# EEPROM_ONLY_memory_board.net
KiCad netlist of a schematic drawn in EAGLE
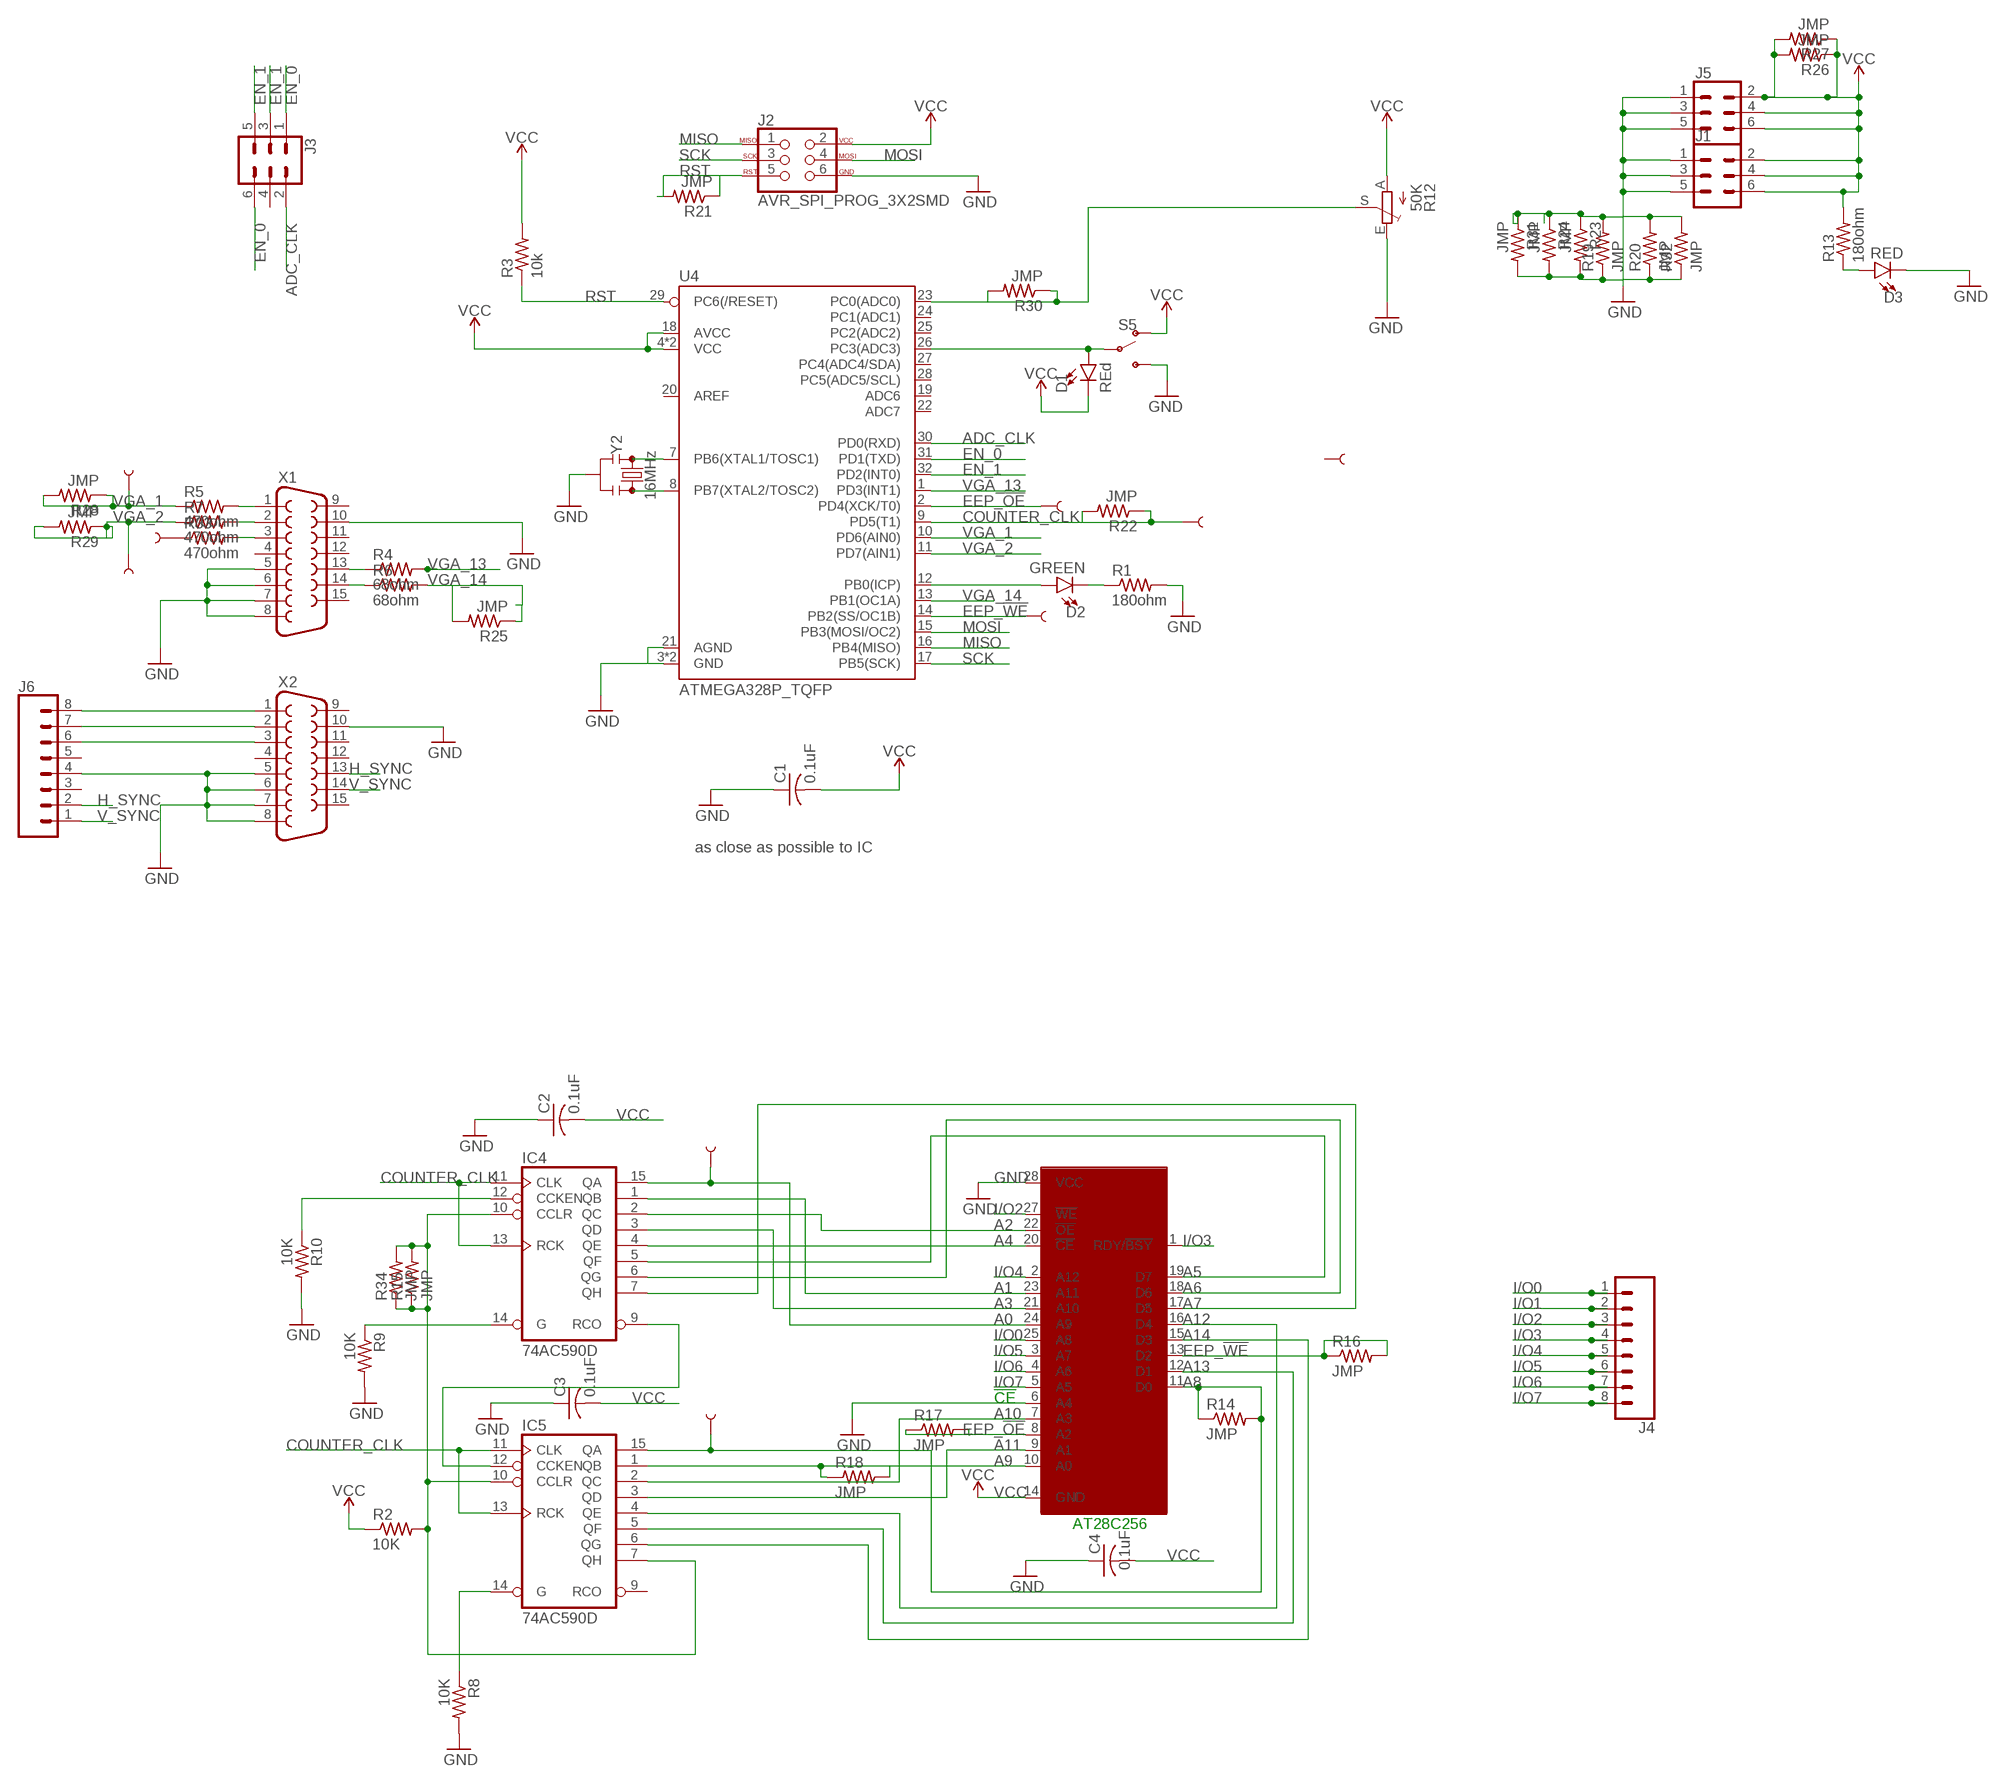
[diagram p0: schematic, sheet 1]

(export (version "E")
  (design (tool "Eeschema 10.0.6"))
  (components
    (comp (ref "C1")
      (value "0.1uF")
      (footprint "eagle-import:C1206")
      (libsource (lib "eagle-import") (part "C-USC1206"))
    )
    (comp (ref "C2")
      (value "0.1uF")
      (footprint "eagle-import:C1206")
      (libsource (lib "eagle-import") (part "C-USC1206"))
    )
    (comp (ref "C3")
      (value "0.1uF")
      (footprint "eagle-import:C1206")
      (libsource (lib "eagle-import") (part "C-USC1206"))
    )
    (comp (ref "C4")
      (value "0.1uF")
      (footprint "eagle-import:C1206")
      (libsource (lib "eagle-import") (part "C-USC1206"))
    )
    (comp (ref "D1")
      (value "REd")
      (footprint "eagle-import:LED-1206")
      (libsource (lib "eagle-import") (part "LED-RED1206"))
    )
    (comp (ref "D2")
      (value "GREEN")
      (footprint "eagle-import:LED-1206")
      (libsource (lib "eagle-import") (part "LED-RED1206"))
    )
    (comp (ref "D3")
      (value "RED")
      (footprint "eagle-import:LED-1206")
      (libsource (lib "eagle-import") (part "LED-RED1206"))
    )
    (comp (ref "IC1")
      (value "28C64AVS")
      (footprint "eagle-import:VSOP28-8X13")
      (libsource (lib "eagle-import") (part "2864AVSC"))
    )
    (comp (ref "IC4")
      (value "74AC590D")
      (footprint "eagle-import:SO16")
      (libsource (lib "eagle-import") (part "74590DAC"))
    )
    (comp (ref "IC5")
      (value "74AC590D")
      (footprint "eagle-import:SO16")
      (libsource (lib "eagle-import") (part "74590DAC"))
    )
    (comp (ref "J1")
      (value "CONN_03X2FEMALE_SMD")
      (footprint "eagle-import:2X3_SMD")
      (libsource (lib "eagle-import") (part "CONN_03X2FEMALE_SMD"))
    )
    (comp (ref "J2")
      (value "AVR_SPI_PROG_3X2SMD")
      (footprint "eagle-import:2X3_SMT_POSTS")
      (libsource (lib "eagle-import") (part "AVR_SPI_PROG_3X2SMD"))
    )
    (comp (ref "J3")
      (value "CONN_03X2FEMALE_SMD")
      (footprint "eagle-import:2X3_SMD")
      (libsource (lib "eagle-import") (part "CONN_03X2FEMALE_SMD"))
    )
    (comp (ref "J4")
      (value "CONN_08SMD-STRAIGHT-ALT-FEMALE")
      (footprint "eagle-import:1X08_SMD_ALT")
      (libsource (lib "eagle-import") (part "CONN_08SMD-STRAIGHT-ALT-FEMALE"))
    )
    (comp (ref "J5")
      (value "CONN_03X2FEMALE_SMD")
      (footprint "eagle-import:2X3_SMD")
      (libsource (lib "eagle-import") (part "CONN_03X2FEMALE_SMD"))
    )
    (comp (ref "J6")
      (value "CONN_08SMD-STRAIGHT-ALT-FEMALE")
      (footprint "eagle-import:1X08_SMD_ALT")
      (libsource (lib "eagle-import") (part "CONN_08SMD-STRAIGHT-ALT-FEMALE"))
    )
    (comp (ref "R1")
      (value "180ohm")
      (footprint "eagle-import:R1206")
      (libsource (lib "eagle-import") (part "R-US_R1206"))
    )
    (comp (ref "R2")
      (value "10K")
      (footprint "eagle-import:R1206")
      (libsource (lib "eagle-import") (part "R-US_R1206"))
    )
    (comp (ref "R3")
      (value "10k")
      (footprint "eagle-import:R1206")
      (libsource (lib "eagle-import") (part "R-US_R1206"))
    )
    (comp (ref "R4")
      (value "68ohm")
      (footprint "eagle-import:R1206")
      (libsource (lib "eagle-import") (part "R-US_R1206"))
    )
    (comp (ref "R5")
      (value "470ohm")
      (footprint "eagle-import:R1206")
      (libsource (lib "eagle-import") (part "R-US_R1206"))
    )
    (comp (ref "R6")
      (value "68ohm")
      (footprint "eagle-import:R1206")
      (libsource (lib "eagle-import") (part "R-US_R1206"))
    )
    (comp (ref "R7")
      (value "470ohm")
      (footprint "eagle-import:R1206")
      (libsource (lib "eagle-import") (part "R-US_R1206"))
    )
    (comp (ref "R8")
      (value "10K")
      (footprint "eagle-import:R1206")
      (libsource (lib "eagle-import") (part "R-US_R1206"))
    )
    (comp (ref "R9")
      (value "10K")
      (footprint "eagle-import:R1206")
      (libsource (lib "eagle-import") (part "R-US_R1206"))
    )
    (comp (ref "R10")
      (value "10K")
      (footprint "eagle-import:R1206")
      (libsource (lib "eagle-import") (part "R-US_R1206"))
    )
    (comp (ref "R12")
      (value "50K")
      (footprint "eagle-import:CA9V")
      (libsource (lib "eagle-import") (part "TRIM_EU-CA9V"))
    )
    (comp (ref "R13")
      (value "180ohm")
      (footprint "eagle-import:R1206")
      (libsource (lib "eagle-import") (part "R-US_R1206"))
    )
    (comp (ref "R14")
      (value "JMP")
      (footprint "eagle-import:R1206")
      (libsource (lib "eagle-import") (part "R-US_R1206"))
    )
    (comp (ref "R15")
      (value "JMP")
      (footprint "eagle-import:R1206")
      (libsource (lib "eagle-import") (part "R-US_R1206"))
    )
    (comp (ref "R16")
      (value "JMP")
      (footprint "eagle-import:R1206")
      (libsource (lib "eagle-import") (part "R-US_R1206"))
    )
    (comp (ref "R17")
      (value "JMP")
      (footprint "eagle-import:R1206")
      (libsource (lib "eagle-import") (part "R-US_R1206"))
    )
    (comp (ref "R18")
      (value "JMP")
      (footprint "eagle-import:R1206")
      (libsource (lib "eagle-import") (part "R-US_R1206"))
    )
    (comp (ref "R19")
      (value "JMP")
      (footprint "eagle-import:R1206")
      (libsource (lib "eagle-import") (part "R-US_R1206"))
    )
    (comp (ref "R20")
      (value "JMP")
      (footprint "eagle-import:R1206")
      (libsource (lib "eagle-import") (part "R-US_R1206"))
    )
    (comp (ref "R21")
      (value "JMP")
      (footprint "eagle-import:R1206")
      (libsource (lib "eagle-import") (part "R-US_R1206"))
    )
    (comp (ref "R22")
      (value "JMP")
      (footprint "eagle-import:R1206")
      (libsource (lib "eagle-import") (part "R-US_R1206"))
    )
    (comp (ref "R23")
      (value "JMP")
      (footprint "eagle-import:R1206")
      (libsource (lib "eagle-import") (part "R-US_R1206"))
    )
    (comp (ref "R24")
      (value "JMP")
      (footprint "eagle-import:R1206")
      (libsource (lib "eagle-import") (part "R-US_R1206"))
    )
    (comp (ref "R25")
      (value "JMP")
      (footprint "eagle-import:R1206")
      (libsource (lib "eagle-import") (part "R-US_R1206"))
    )
    (comp (ref "R26")
      (value "JMP")
      (footprint "eagle-import:R1206")
      (libsource (lib "eagle-import") (part "R-US_R1206"))
    )
    (comp (ref "R27")
      (value "JMP")
      (footprint "eagle-import:R1206")
      (libsource (lib "eagle-import") (part "R-US_R1206"))
    )
    (comp (ref "R28")
      (value "JMP")
      (footprint "eagle-import:R1206")
      (libsource (lib "eagle-import") (part "R-US_R1206"))
    )
    (comp (ref "R29")
      (value "JMP")
      (footprint "eagle-import:R1206")
      (libsource (lib "eagle-import") (part "R-US_R1206"))
    )
    (comp (ref "R30")
      (value "JMP")
      (footprint "eagle-import:R1206")
      (libsource (lib "eagle-import") (part "R-US_R1206"))
    )
    (comp (ref "R31")
      (value "JMP")
      (footprint "eagle-import:R1206")
      (libsource (lib "eagle-import") (part "R-US_R1206"))
    )
    (comp (ref "R32")
      (value "JMP")
      (footprint "eagle-import:R1206")
      (libsource (lib "eagle-import") (part "R-US_R1206"))
    )
    (comp (ref "R33")
      (value "470ohm")
      (footprint "eagle-import:R1206")
      (libsource (lib "eagle-import") (part "R-US_R1206"))
    )
    (comp (ref "R34")
      (value "JMP")
      (footprint "eagle-import:R1206")
      (libsource (lib "eagle-import") (part "R-US_R1206"))
    )
    (comp (ref "RX1")
      (value "TEST-POINT3")
      (footprint "eagle-import:PAD.03X.03")
      (libsource (lib "eagle-import") (part "TEST-POINT3"))
    )
    (comp (ref "RX2")
      (value "TEST-POINT3")
      (footprint "eagle-import:PAD.03X.03")
      (libsource (lib "eagle-import") (part "TEST-POINT3"))
    )
    (comp (ref "RX3")
      (value "TEST-POINT3")
      (footprint "eagle-import:PAD.03X.03")
      (libsource (lib "eagle-import") (part "TEST-POINT3"))
    )
    (comp (ref "RX4")
      (value "TEST-POINT3")
      (footprint "eagle-import:PAD.03X.03")
      (libsource (lib "eagle-import") (part "TEST-POINT3"))
    )
    (comp (ref "RX5")
      (value "TEST-POINT3")
      (footprint "eagle-import:PAD.03X.03")
      (libsource (lib "eagle-import") (part "TEST-POINT3"))
    )
    (comp (ref "RX6")
      (value "TEST-POINT3")
      (footprint "eagle-import:PAD.03X.03")
      (libsource (lib "eagle-import") (part "TEST-POINT3"))
    )
    (comp (ref "RX7")
      (value "TEST-POINT3")
      (footprint "eagle-import:PAD.03X.03")
      (libsource (lib "eagle-import") (part "TEST-POINT3"))
    )
    (comp (ref "RX8")
      (value "TEST-POINT3")
      (footprint "eagle-import:PAD.03X.03")
      (libsource (lib "eagle-import") (part "TEST-POINT3"))
    )
    (comp (ref "RX9")
      (value "TEST-POINT3")
      (footprint "eagle-import:PAD.03X.03")
      (libsource (lib "eagle-import") (part "TEST-POINT3"))
    )
    (comp (ref "S5")
      (value "SWITCH-SPDT-SMD-AYZ0202")
      (footprint "eagle-import:SWITCH_DPDT_SMD_AYZ0202")
      (libsource (lib "eagle-import") (part "SWITCH-SPDT-SMD-AYZ0202"))
    )
    (comp (ref "U4")
      (value "ATMEGA328P_TQFP")
      (footprint "eagle-import:TQFP32-08")
      (libsource (lib "eagle-import") (part "ATMEGA328P_TQFP"))
    )
    (comp (ref "X1")
      (value "F15HP")
      (footprint "eagle-import:F15HP")
      (libsource (lib "eagle-import") (part "F15HP"))
    )
    (comp (ref "X2")
      (value "F15HP")
      (footprint "eagle-import:F15HP")
      (libsource (lib "eagle-import") (part "F15HP"))
    )
    (comp (ref "Y2")
      (value "16MHz")
      (footprint "eagle-import:RESONATOR-SMD-3.2X1.3")
      (libsource (lib "eagle-import") (part "RESONATOR-16MHZSMD_3.2X1.3"))
    )
  )
  (nets
    (net (code "1") (name "/A0") (class "Default")
      (node (ref "IC1") (pin "24") (pinfunction "A9_24") (pintype "input"))
      (node (ref "IC4") (pin "15") (pinfunction "QA_15") (pintype "tri_state"))
      (node (ref "RX5") (pin "P$1") (pinfunction "1_P$1") (pintype "bidirectional"))
    )
    (net (code "2") (name "/A1") (class "Default")
      (node (ref "IC1") (pin "23") (pinfunction "A11_23") (pintype "input"))
      (node (ref "IC4") (pin "1") (pinfunction "QB_1") (pintype "tri_state"))
    )
    (net (code "3") (name "/A2") (class "Default")
      (node (ref "IC1") (pin "22") (pinfunction "~{OE}_22") (pintype "input"))
      (node (ref "IC4") (pin "2") (pinfunction "QC_2") (pintype "tri_state"))
    )
    (net (code "4") (name "/A3") (class "Default")
      (node (ref "IC1") (pin "21") (pinfunction "A10_21") (pintype "input"))
      (node (ref "IC4") (pin "3") (pinfunction "QD_3") (pintype "tri_state"))
    )
    (net (code "5") (name "/A4") (class "Default")
      (node (ref "IC1") (pin "20") (pinfunction "~{CE}_20") (pintype "input"))
      (node (ref "IC4") (pin "4") (pinfunction "QE_4") (pintype "tri_state"))
    )
    (net (code "6") (name "/A5") (class "Default")
      (node (ref "IC1") (pin "19") (pinfunction "D7_19") (pintype "tri_state"))
      (node (ref "IC4") (pin "5") (pinfunction "QF_5") (pintype "tri_state"))
    )
    (net (code "7") (name "/A6") (class "Default")
      (node (ref "IC1") (pin "18") (pinfunction "D6_18") (pintype "tri_state"))
      (node (ref "IC4") (pin "6") (pinfunction "QG_6") (pintype "tri_state"))
    )
    (net (code "8") (name "/A7") (class "Default")
      (node (ref "IC1") (pin "17") (pinfunction "D5_17") (pintype "tri_state"))
      (node (ref "IC4") (pin "7") (pinfunction "QH_7") (pintype "tri_state"))
    )
    (net (code "9") (name "/A8") (class "Default")
      (node (ref "IC1") (pin "11") (pinfunction "D0_11") (pintype "tri_state"))
      (node (ref "IC5") (pin "15") (pinfunction "QA_15") (pintype "tri_state"))
      (node (ref "R14") (pin "1") (pinfunction "1_1") (pintype "passive"))
      (node (ref "R14") (pin "2") (pinfunction "2_2") (pintype "passive"))
      (node (ref "RX6") (pin "P$1") (pinfunction "1_P$1") (pintype "bidirectional"))
    )
    (net (code "10") (name "/A9") (class "Default")
      (node (ref "IC1") (pin "10") (pinfunction "A0_10") (pintype "input"))
      (node (ref "IC5") (pin "1") (pinfunction "QB_1") (pintype "tri_state"))
      (node (ref "R18") (pin "1") (pinfunction "1_1") (pintype "passive"))
      (node (ref "R18") (pin "2") (pinfunction "2_2") (pintype "passive"))
    )
    (net (code "11") (name "/A10") (class "Default")
      (node (ref "IC1") (pin "7") (pinfunction "A3_7") (pintype "input"))
      (node (ref "IC5") (pin "2") (pinfunction "QC_2") (pintype "tri_state"))
    )
    (net (code "12") (name "/A11") (class "Default")
      (node (ref "IC1") (pin "9") (pinfunction "A1_9") (pintype "input"))
      (node (ref "IC5") (pin "3") (pinfunction "QD_3") (pintype "tri_state"))
    )
    (net (code "13") (name "/A12") (class "Default")
      (node (ref "IC1") (pin "16") (pinfunction "D4_16") (pintype "tri_state"))
      (node (ref "IC5") (pin "4") (pinfunction "QE_4") (pintype "tri_state"))
    )
    (net (code "14") (name "/A13") (class "Default")
      (node (ref "IC1") (pin "12") (pinfunction "D1_12") (pintype "tri_state"))
      (node (ref "IC5") (pin "5") (pinfunction "QF_5") (pintype "tri_state"))
    )
    (net (code "15") (name "/A14") (class "Default")
      (node (ref "IC1") (pin "15") (pinfunction "D3_15") (pintype "tri_state"))
      (node (ref "IC5") (pin "6") (pinfunction "QG_6") (pintype "tri_state"))
    )
    (net (code "16") (name "/ADC_CLK") (class "Default")
      (node (ref "J3") (pin "2") (pinfunction "2_2") (pintype "bidirectional"))
      (node (ref "U4") (pin "30") (pinfunction "PD0(RXD)_30") (pintype "bidirectional"))
    )
    (net (code "17") (name "/COUNTER_CLK") (class "Default")
      (node (ref "IC4") (pin "11") (pinfunction "CLK_11") (pintype "input"))
      (node (ref "IC4") (pin "13") (pinfunction "RCK_13") (pintype "input"))
      (node (ref "IC5") (pin "11") (pinfunction "CLK_11") (pintype "input"))
      (node (ref "IC5") (pin "13") (pinfunction "RCK_13") (pintype "input"))
      (node (ref "R22") (pin "1") (pinfunction "1_1") (pintype "passive"))
      (node (ref "R22") (pin "2") (pinfunction "2_2") (pintype "passive"))
      (node (ref "RX3") (pin "P$1") (pinfunction "1_P$1") (pintype "bidirectional"))
      (node (ref "U4") (pin "9") (pinfunction "PD5(T1)_9") (pintype "bidirectional"))
    )
    (net (code "18") (name "/EEP_~{OE}") (class "Default")
      (node (ref "IC1") (pin "8") (pinfunction "A2_8") (pintype "input"))
      (node (ref "R17") (pin "1") (pinfunction "1_1") (pintype "passive"))
      (node (ref "R17") (pin "2") (pinfunction "2_2") (pintype "passive"))
      (node (ref "RX2") (pin "P$1") (pinfunction "1_P$1") (pintype "bidirectional"))
      (node (ref "U4") (pin "2") (pinfunction "PD4(XCK/T0)_2") (pintype "bidirectional"))
    )
    (net (code "19") (name "/EEP_~{WE}") (class "Default")
      (node (ref "IC1") (pin "13") (pinfunction "D2_13") (pintype "tri_state"))
      (node (ref "R16") (pin "1") (pinfunction "1_1") (pintype "passive"))
      (node (ref "R16") (pin "2") (pinfunction "2_2") (pintype "passive"))
      (node (ref "RX4") (pin "P$1") (pinfunction "1_P$1") (pintype "bidirectional"))
      (node (ref "U4") (pin "14") (pinfunction "PB2(SS/OC1B)_14") (pintype "bidirectional"))
    )
    (net (code "20") (name "/EN_0") (class "Default")
      (node (ref "J3") (pin "1") (pinfunction "1_1") (pintype "bidirectional"))
      (node (ref "J3") (pin "6") (pinfunction "6_6") (pintype "bidirectional"))
      (node (ref "U4") (pin "31") (pinfunction "PD1(TXD)_31") (pintype "bidirectional"))
    )
    (net (code "21") (name "/EN_1") (class "Default")
      (node (ref "J3") (pin "3") (pinfunction "3_3") (pintype "bidirectional"))
      (node (ref "J3") (pin "5") (pinfunction "5_5") (pintype "bidirectional"))
      (node (ref "U4") (pin "32") (pinfunction "PD2(INT0)_32") (pintype "bidirectional"))
    )
    (net (code "22") (name "/H_SYNC") (class "Default")
      (node (ref "J6") (pin "2") (pinfunction "2_2") (pintype "passive"))
      (node (ref "X2") (pin "13") (pinfunction "13_13") (pintype "passive"))
    )
    (net (code "23") (name "/I{slash}O0") (class "Default")
      (node (ref "IC1") (pin "25") (pinfunction "A8_25") (pintype "input"))
      (node (ref "J4") (pin "1") (pinfunction "1_1") (pintype "passive"))
    )
    (net (code "24") (name "/I{slash}O1") (class "Default")
      (node (ref "J4") (pin "2") (pinfunction "2_2") (pintype "passive"))
    )
    (net (code "25") (name "/I{slash}O2") (class "Default")
      (node (ref "IC1") (pin "27") (pinfunction "~{WE}_27") (pintype "input"))
      (node (ref "J4") (pin "3") (pinfunction "3_3") (pintype "passive"))
    )
    (net (code "26") (name "/I{slash}O3") (class "Default")
      (node (ref "IC1") (pin "1") (pinfunction "RDY/~{BSY}_1") (pintype "output"))
      (node (ref "J4") (pin "4") (pinfunction "4_4") (pintype "passive"))
    )
    (net (code "27") (name "/I{slash}O4") (class "Default")
      (node (ref "IC1") (pin "2") (pinfunction "A12_2") (pintype "input"))
      (node (ref "J4") (pin "5") (pinfunction "5_5") (pintype "passive"))
    )
    (net (code "28") (name "/I{slash}O5") (class "Default")
      (node (ref "IC1") (pin "3") (pinfunction "A7_3") (pintype "input"))
      (node (ref "J4") (pin "6") (pinfunction "6_6") (pintype "passive"))
    )
    (net (code "29") (name "/I{slash}O6") (class "Default")
      (node (ref "IC1") (pin "4") (pinfunction "A6_4") (pintype "input"))
      (node (ref "J4") (pin "7") (pinfunction "7_7") (pintype "passive"))
    )
    (net (code "30") (name "/I{slash}O7") (class "Default")
      (node (ref "IC1") (pin "5") (pinfunction "A5_5") (pintype "input"))
      (node (ref "J4") (pin "8") (pinfunction "8_8") (pintype "passive"))
    )
    (net (code "31") (name "/MISO") (class "Default")
      (node (ref "J2") (pin "1") (pinfunction "1_1") (pintype "passive"))
      (node (ref "U4") (pin "16") (pinfunction "PB4(MISO)_16") (pintype "bidirectional"))
    )
    (net (code "32") (name "/MOSI") (class "Default")
      (node (ref "J2") (pin "4") (pinfunction "4_4") (pintype "passive"))
      (node (ref "U4") (pin "15") (pinfunction "PB3(MOSI/OC2)_15") (pintype "bidirectional"))
    )
    (net (code "33") (name "/RST") (class "Default")
      (node (ref "J2") (pin "5") (pinfunction "5_5") (pintype "passive"))
      (node (ref "R21") (pin "1") (pinfunction "1_1") (pintype "passive"))
      (node (ref "R21") (pin "2") (pinfunction "2_2") (pintype "passive"))
      (node (ref "R3") (pin "1") (pinfunction "1_1") (pintype "passive"))
      (node (ref "U4") (pin "29") (pinfunction "PC6(/RESET)_29") (pintype "bidirectional"))
    )
    (net (code "34") (name "/SCK") (class "Default")
      (node (ref "J2") (pin "3") (pinfunction "3_3") (pintype "passive"))
      (node (ref "U4") (pin "17") (pinfunction "PB5(SCK)_17") (pintype "bidirectional"))
    )
    (net (code "35") (name "/VGA_1") (class "Default")
      (node (ref "R28") (pin "1") (pinfunction "1_1") (pintype "passive"))
      (node (ref "R28") (pin "2") (pinfunction "2_2") (pintype "passive"))
      (node (ref "R5") (pin "1") (pinfunction "1_1") (pintype "passive"))
      (node (ref "RX8") (pin "P$1") (pinfunction "1_P$1") (pintype "bidirectional"))
      (node (ref "U4") (pin "10") (pinfunction "PD6(AIN0)_10") (pintype "bidirectional"))
    )
    (net (code "36") (name "/VGA_2") (class "Default")
      (node (ref "R29") (pin "1") (pinfunction "1_1") (pintype "passive"))
      (node (ref "R29") (pin "2") (pinfunction "2_2") (pintype "passive"))
      (node (ref "R7") (pin "1") (pinfunction "1_1") (pintype "passive"))
      (node (ref "RX9") (pin "P$1") (pinfunction "1_P$1") (pintype "bidirectional"))
      (node (ref "U4") (pin "11") (pinfunction "PD7(AIN1)_11") (pintype "bidirectional"))
    )
    (net (code "37") (name "/VGA_13") (class "Default")
      (node (ref "R4") (pin "2") (pinfunction "2_2") (pintype "passive"))
      (node (ref "U4") (pin "1") (pinfunction "PD3(INT1)_1") (pintype "bidirectional"))
    )
    (net (code "38") (name "/VGA_14") (class "Default")
      (node (ref "R25") (pin "1") (pinfunction "1_1") (pintype "passive"))
      (node (ref "R25") (pin "2") (pinfunction "2_2") (pintype "passive"))
      (node (ref "R6") (pin "2") (pinfunction "2_2") (pintype "passive"))
      (node (ref "U4") (pin "13") (pinfunction "PB1(OC1A)_13") (pintype "bidirectional"))
    )
    (net (code "39") (name "/V_SYNC") (class "Default")
      (node (ref "J6") (pin "1") (pinfunction "1_1") (pintype "passive"))
      (node (ref "X2") (pin "14") (pinfunction "14_14") (pintype "passive"))
    )
    (net (code "40") (name "GND") (class "Default")
      (node (ref "C1") (pin "1") (pinfunction "1_1") (pintype "passive"))
      (node (ref "C2") (pin "1") (pinfunction "1_1") (pintype "passive"))
      (node (ref "C3") (pin "1") (pinfunction "1_1") (pintype "passive"))
      (node (ref "C4") (pin "1") (pinfunction "1_1") (pintype "passive"))
      (node (ref "D3") (pin "C") (pinfunction "C_C") (pintype "passive"))
      (node (ref "IC1") (pin "28") (pinfunction "VCC_28") (pintype "power_in"))
      (node (ref "IC1") (pin "6") (pinfunction "A4_6") (pintype "input"))
      (node (ref "J1") (pin "1") (pinfunction "1_1") (pintype "bidirectional"))
      (node (ref "J1") (pin "3") (pinfunction "3_3") (pintype "bidirectional"))
      (node (ref "J1") (pin "5") (pinfunction "5_5") (pintype "bidirectional"))
      (node (ref "J2") (pin "6") (pinfunction "6_6") (pintype "passive"))
      (node (ref "J5") (pin "1") (pinfunction "1_1") (pintype "bidirectional"))
      (node (ref "J5") (pin "3") (pinfunction "3_3") (pintype "bidirectional"))
      (node (ref "J5") (pin "5") (pinfunction "5_5") (pintype "bidirectional"))
      (node (ref "J6") (pin "4") (pinfunction "4_4") (pintype "passive"))
      (node (ref "R1") (pin "2") (pinfunction "2_2") (pintype "passive"))
      (node (ref "R10") (pin "2") (pinfunction "2_2") (pintype "passive"))
      (node (ref "R12") (pin "E") (pinfunction "E_E") (pintype "passive"))
      (node (ref "R19") (pin "1") (pinfunction "1_1") (pintype "passive"))
      (node (ref "R19") (pin "2") (pinfunction "2_2") (pintype "passive"))
      (node (ref "R20") (pin "1") (pinfunction "1_1") (pintype "passive"))
      (node (ref "R20") (pin "2") (pinfunction "2_2") (pintype "passive"))
      (node (ref "R23") (pin "1") (pinfunction "1_1") (pintype "passive"))
      (node (ref "R23") (pin "2") (pinfunction "2_2") (pintype "passive"))
      (node (ref "R24") (pin "1") (pinfunction "1_1") (pintype "passive"))
      (node (ref "R24") (pin "2") (pinfunction "2_2") (pintype "passive"))
      (node (ref "R31") (pin "1") (pinfunction "1_1") (pintype "passive"))
      (node (ref "R31") (pin "2") (pinfunction "2_2") (pintype "passive"))
      (node (ref "R32") (pin "1") (pinfunction "1_1") (pintype "passive"))
      (node (ref "R32") (pin "2") (pinfunction "2_2") (pintype "passive"))
      (node (ref "R8") (pin "2") (pinfunction "2_2") (pintype "passive"))
      (node (ref "R9") (pin "2") (pinfunction "2_2") (pintype "passive"))
      (node (ref "S5") (pin "3") (pinfunction "S_3") (pintype "passive"))
      (node (ref "U4") (pin "21") (pinfunction "AGND_21") (pintype "bidirectional"))
      (node (ref "U4") (pin "3") (pinfunction "GND_3") (pintype "bidirectional"))
      (node (ref "U4") (pin "5") (pinfunction "GND_5") (pintype "bidirectional"))
      (node (ref "X1") (pin "10") (pinfunction "10_10") (pintype "passive"))
      (node (ref "X1") (pin "5") (pinfunction "5_5") (pintype "passive"))
      (node (ref "X1") (pin "6") (pinfunction "6_6") (pintype "passive"))
      (node (ref "X1") (pin "7") (pinfunction "7_7") (pintype "passive"))
      (node (ref "X1") (pin "8") (pinfunction "8_8") (pintype "passive"))
      (node (ref "X2") (pin "10") (pinfunction "10_10") (pintype "passive"))
      (node (ref "X2") (pin "5") (pinfunction "5_5") (pintype "passive"))
      (node (ref "X2") (pin "6") (pinfunction "6_6") (pintype "passive"))
      (node (ref "X2") (pin "7") (pinfunction "7_7") (pintype "passive"))
      (node (ref "X2") (pin "8") (pinfunction "8_8") (pintype "passive"))
      (node (ref "Y2") (pin "2") (pinfunction "2_2") (pintype "passive"))
    )
    (net (code "41") (name "Net-(D2-PadC)") (class "Default")
      (node (ref "D2") (pin "C") (pinfunction "C_C") (pintype "passive"))
      (node (ref "R1") (pin "1") (pinfunction "1_1") (pintype "passive"))
    )
    (net (code "42") (name "Net-(D3-PadA)") (class "Default")
      (node (ref "D3") (pin "A") (pinfunction "A_A") (pintype "passive"))
      (node (ref "R13") (pin "1") (pinfunction "1_1") (pintype "passive"))
    )
    (net (code "43") (name "Net-(IC4A-CCKEN)") (class "Default")
      (node (ref "IC4") (pin "12") (pinfunction "CCKEN_12") (pintype "input"))
      (node (ref "R10") (pin "1") (pinfunction "1_1") (pintype "passive"))
    )
    (net (code "44") (name "Net-(IC4A-CCLR)") (class "Default")
      (node (ref "IC4") (pin "10") (pinfunction "CCLR_10") (pintype "input"))
      (node (ref "IC5") (pin "10") (pinfunction "CCLR_10") (pintype "input"))
      (node (ref "IC5") (pin "7") (pinfunction "QH_7") (pintype "tri_state"))
      (node (ref "R15") (pin "1") (pinfunction "1_1") (pintype "passive"))
      (node (ref "R15") (pin "2") (pinfunction "2_2") (pintype "passive"))
      (node (ref "R2") (pin "2") (pinfunction "2_2") (pintype "passive"))
      (node (ref "R34") (pin "1") (pinfunction "1_1") (pintype "passive"))
      (node (ref "R34") (pin "2") (pinfunction "2_2") (pintype "passive"))
    )
    (net (code "45") (name "Net-(IC4A-G)") (class "Default")
      (node (ref "IC4") (pin "14") (pinfunction "G_14") (pintype "input"))
      (node (ref "R9") (pin "1") (pinfunction "1_1") (pintype "passive"))
    )
    (net (code "46") (name "Net-(IC4A-RCO)") (class "Default")
      (node (ref "IC4") (pin "9") (pinfunction "RCO_9") (pintype "output"))
      (node (ref "IC5") (pin "12") (pinfunction "CCKEN_12") (pintype "input"))
    )
    (net (code "47") (name "Net-(IC5A-G)") (class "Default")
      (node (ref "IC5") (pin "14") (pinfunction "G_14") (pintype "input"))
      (node (ref "R8") (pin "1") (pinfunction "1_1") (pintype "passive"))
    )
    (net (code "48") (name "Net-(J6-Pad6)") (class "Default")
      (node (ref "J6") (pin "6") (pinfunction "6_6") (pintype "passive"))
      (node (ref "X2") (pin "3") (pinfunction "3_3") (pintype "passive"))
    )
    (net (code "49") (name "Net-(J6-Pad7)") (class "Default")
      (node (ref "J6") (pin "7") (pinfunction "7_7") (pintype "passive"))
      (node (ref "X2") (pin "2") (pinfunction "2_2") (pintype "passive"))
    )
    (net (code "50") (name "Net-(J6-Pad8)") (class "Default")
      (node (ref "J6") (pin "8") (pinfunction "8_8") (pintype "passive"))
      (node (ref "X2") (pin "1") (pinfunction "1_1") (pintype "passive"))
    )
    (net (code "51") (name "Net-(R4-Pad1)") (class "Default")
      (node (ref "R4") (pin "1") (pinfunction "1_1") (pintype "passive"))
      (node (ref "X1") (pin "13") (pinfunction "13_13") (pintype "passive"))
    )
    (net (code "52") (name "Net-(R5-Pad2)") (class "Default")
      (node (ref "R5") (pin "2") (pinfunction "2_2") (pintype "passive"))
      (node (ref "X1") (pin "1") (pinfunction "1_1") (pintype "passive"))
    )
    (net (code "53") (name "Net-(R6-Pad1)") (class "Default")
      (node (ref "R6") (pin "1") (pinfunction "1_1") (pintype "passive"))
      (node (ref "X1") (pin "14") (pinfunction "14_14") (pintype "passive"))
    )
    (net (code "54") (name "Net-(R7-Pad2)") (class "Default")
      (node (ref "R7") (pin "2") (pinfunction "2_2") (pintype "passive"))
      (node (ref "X1") (pin "2") (pinfunction "2_2") (pintype "passive"))
    )
    (net (code "55") (name "Net-(R33-Pad2)") (class "Default")
      (node (ref "R33") (pin "2") (pinfunction "2_2") (pintype "passive"))
      (node (ref "X1") (pin "3") (pinfunction "3_3") (pintype "passive"))
    )
    (net (code "56") (name "Net-(RX7-1)") (class "Default")
      (node (ref "R33") (pin "1") (pinfunction "1_1") (pintype "passive"))
      (node (ref "RX7") (pin "P$1") (pinfunction "1_P$1") (pintype "bidirectional"))
    )
    (net (code "57") (name "Net-(S5-P)") (class "Default")
      (node (ref "D1") (pin "A") (pinfunction "A_A") (pintype "passive"))
      (node (ref "S5") (pin "2") (pinfunction "P_2") (pintype "passive"))
      (node (ref "U4") (pin "26") (pinfunction "PC3(ADC3)_26") (pintype "bidirectional"))
    )
    (net (code "58") (name "Net-(U4-PB0(ICP))") (class "Default")
      (node (ref "D2") (pin "A") (pinfunction "A_A") (pintype "passive"))
      (node (ref "U4") (pin "12") (pinfunction "PB0(ICP)_12") (pintype "bidirectional"))
    )
    (net (code "59") (name "Net-(U4-PB6(XTAL1{slash}TOSC1))") (class "Default")
      (node (ref "U4") (pin "7") (pinfunction "PB6(XTAL1/TOSC1)_7") (pintype "bidirectional"))
      (node (ref "Y2") (pin "1") (pinfunction "1_1") (pintype "passive"))
    )
    (net (code "60") (name "Net-(U4-PB7(XTAL2{slash}TOSC2))") (class "Default")
      (node (ref "U4") (pin "8") (pinfunction "PB7(XTAL2/TOSC2)_8") (pintype "bidirectional"))
      (node (ref "Y2") (pin "3") (pinfunction "3_3") (pintype "passive"))
    )
    (net (code "61") (name "Net-(U4-PC0(ADC0))") (class "Default")
      (node (ref "R12") (pin "S") (pinfunction "S_S") (pintype "passive"))
      (node (ref "R30") (pin "1") (pinfunction "1_1") (pintype "passive"))
      (node (ref "R30") (pin "2") (pinfunction "2_2") (pintype "passive"))
      (node (ref "U4") (pin "23") (pinfunction "PC0(ADC0)_23") (pintype "bidirectional"))
    )
    (net (code "62") (name "VCC") (class "Default")
      (node (ref "C1") (pin "2") (pinfunction "2_2") (pintype "passive"))
      (node (ref "C2") (pin "2") (pinfunction "2_2") (pintype "passive"))
      (node (ref "C3") (pin "2") (pinfunction "2_2") (pintype "passive"))
      (node (ref "C4") (pin "2") (pinfunction "2_2") (pintype "passive"))
      (node (ref "D1") (pin "C") (pinfunction "C_C") (pintype "passive"))
      (node (ref "IC1") (pin "14") (pinfunction "GND_14") (pintype "power_in"))
      (node (ref "J1") (pin "2") (pinfunction "2_2") (pintype "bidirectional"))
      (node (ref "J1") (pin "4") (pinfunction "4_4") (pintype "bidirectional"))
      (node (ref "J1") (pin "6") (pinfunction "6_6") (pintype "bidirectional"))
      (node (ref "J2") (pin "2") (pinfunction "2_2") (pintype "passive"))
      (node (ref "J5") (pin "2") (pinfunction "2_2") (pintype "bidirectional"))
      (node (ref "J5") (pin "4") (pinfunction "4_4") (pintype "bidirectional"))
      (node (ref "J5") (pin "6") (pinfunction "6_6") (pintype "bidirectional"))
      (node (ref "R12") (pin "A") (pinfunction "A_A") (pintype "passive"))
      (node (ref "R13") (pin "2") (pinfunction "2_2") (pintype "passive"))
      (node (ref "R2") (pin "1") (pinfunction "1_1") (pintype "passive"))
      (node (ref "R26") (pin "1") (pinfunction "1_1") (pintype "passive"))
      (node (ref "R26") (pin "2") (pinfunction "2_2") (pintype "passive"))
      (node (ref "R27") (pin "1") (pinfunction "1_1") (pintype "passive"))
      (node (ref "R27") (pin "2") (pinfunction "2_2") (pintype "passive"))
      (node (ref "R3") (pin "2") (pinfunction "2_2") (pintype "passive"))
      (node (ref "S5") (pin "1") (pinfunction "O_1") (pintype "passive"))
      (node (ref "U4") (pin "18") (pinfunction "AVCC_18") (pintype "bidirectional"))
      (node (ref "U4") (pin "4") (pinfunction "VCC_4") (pintype "bidirectional"))
      (node (ref "U4") (pin "6") (pinfunction "VCC_6") (pintype "bidirectional"))
    )
    (net (code "63") (name "unconnected-(IC5A-RCO-Pad9)") (class "Default")
      (node (ref "IC5") (pin "9") (pinfunction "RCO_9") (pintype "output"))
    )
    (net (code "64") (name "unconnected-(J3-Pad4)") (class "Default")
      (node (ref "J3") (pin "4") (pinfunction "4_4") (pintype "bidirectional"))
    )
    (net (code "65") (name "unconnected-(J6-Pad3)") (class "Default")
      (node (ref "J6") (pin "3") (pinfunction "3_3") (pintype "passive"))
    )
    (net (code "66") (name "unconnected-(J6-Pad5)") (class "Default")
      (node (ref "J6") (pin "5") (pinfunction "5_5") (pintype "passive"))
    )
    (net (code "67") (name "unconnected-(RX1-1-PadP$1)") (class "Default")
      (node (ref "RX1") (pin "P$1") (pinfunction "1_P$1") (pintype "bidirectional"))
    )
    (net (code "68") (name "unconnected-(U4-ADC6-Pad19)") (class "Default")
      (node (ref "U4") (pin "19") (pinfunction "ADC6_19") (pintype "bidirectional"))
    )
    (net (code "69") (name "unconnected-(U4-ADC7-Pad22)") (class "Default")
      (node (ref "U4") (pin "22") (pinfunction "ADC7_22") (pintype "bidirectional"))
    )
    (net (code "70") (name "unconnected-(U4-AREF-Pad20)") (class "Default")
      (node (ref "U4") (pin "20") (pinfunction "AREF_20") (pintype "bidirectional"))
    )
    (net (code "71") (name "unconnected-(U4-PC1(ADC1)-Pad24)") (class "Default")
      (node (ref "U4") (pin "24") (pinfunction "PC1(ADC1)_24") (pintype "bidirectional"))
    )
    (net (code "72") (name "unconnected-(U4-PC2(ADC2)-Pad25)") (class "Default")
      (node (ref "U4") (pin "25") (pinfunction "PC2(ADC2)_25") (pintype "bidirectional"))
    )
    (net (code "73") (name "unconnected-(U4-PC4(ADC4{slash}SDA)-Pad27)") (class "Default")
      (node (ref "U4") (pin "27") (pinfunction "PC4(ADC4/SDA)_27") (pintype "bidirectional"))
    )
    (net (code "74") (name "unconnected-(U4-PC5(ADC5{slash}SCL)-Pad28)") (class "Default")
      (node (ref "U4") (pin "28") (pinfunction "PC5(ADC5/SCL)_28") (pintype "bidirectional"))
    )
    (net (code "75") (name "unconnected-(X1-Pad4)") (class "Default")
      (node (ref "X1") (pin "4") (pinfunction "4_4") (pintype "passive"))
    )
    (net (code "76") (name "unconnected-(X1-Pad9)") (class "Default")
      (node (ref "X1") (pin "9") (pinfunction "9_9") (pintype "passive"))
    )
    (net (code "77") (name "unconnected-(X1-Pad11)") (class "Default")
      (node (ref "X1") (pin "11") (pinfunction "11_11") (pintype "passive"))
    )
    (net (code "78") (name "unconnected-(X1-Pad12)") (class "Default")
      (node (ref "X1") (pin "12") (pinfunction "12_12") (pintype "passive"))
    )
    (net (code "79") (name "unconnected-(X1-Pad15)") (class "Default")
      (node (ref "X1") (pin "15") (pinfunction "15_15") (pintype "passive"))
    )
    (net (code "80") (name "unconnected-(X2-Pad4)") (class "Default")
      (node (ref "X2") (pin "4") (pinfunction "4_4") (pintype "passive"))
    )
    (net (code "81") (name "unconnected-(X2-Pad9)") (class "Default")
      (node (ref "X2") (pin "9") (pinfunction "9_9") (pintype "passive"))
    )
    (net (code "82") (name "unconnected-(X2-Pad11)") (class "Default")
      (node (ref "X2") (pin "11") (pinfunction "11_11") (pintype "passive"))
    )
    (net (code "83") (name "unconnected-(X2-Pad12)") (class "Default")
      (node (ref "X2") (pin "12") (pinfunction "12_12") (pintype "passive"))
    )
    (net (code "84") (name "unconnected-(X2-Pad15)") (class "Default")
      (node (ref "X2") (pin "15") (pinfunction "15_15") (pintype "passive"))
    )
  )
)
